# LB_BIT_i30_KEYBOARD-v03_3_4_-OHW.net
KiCad netlist of a schematic drawn in EAGLE
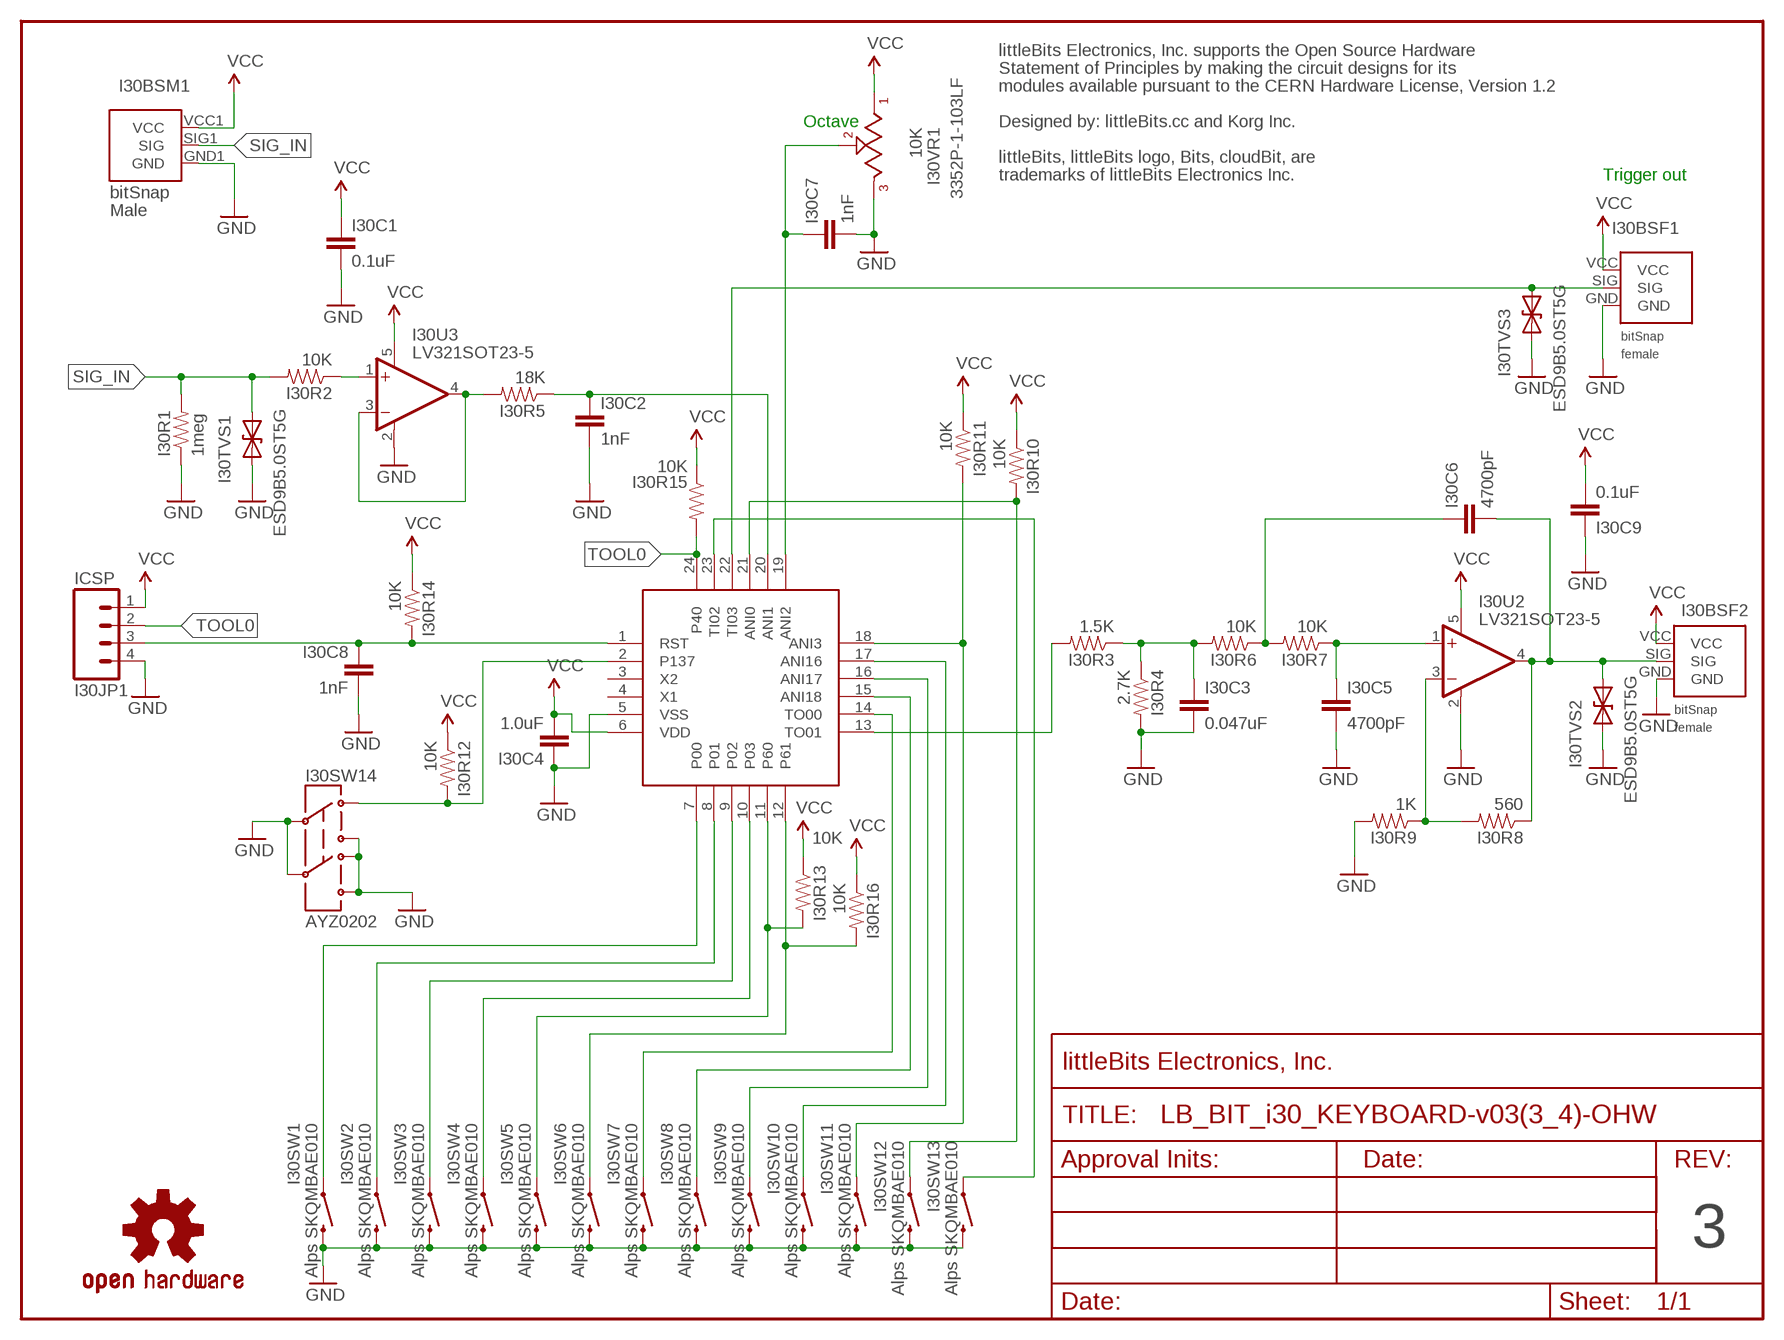
[diagram p0: schematic, sheet 1]

(export (version "E")
  (design (tool "Eeschema 10.0.6"))
  (components
    (comp (ref "FRAME1")
      (value "FRAME-LETTER-OHWOHW")
      (footprint "eagle-import:FABDWG01-OHW")
      (libsource (lib "eagle-import") (part "FRAME-LETTER-OHWOHW"))
    )
    (comp (ref "I30BSF1")
      (value "BITSNAP_V03_FEMALE")
      (footprint "eagle-import:BITSNAP_V03_FEMALE")
      (libsource (lib "eagle-import") (part "BITSNAP_V03_FEMALE"))
    )
    (comp (ref "I30BSF2")
      (value "BITSNAP_V03_FEMALE")
      (footprint "eagle-import:BITSNAP_V03_FEMALE")
      (libsource (lib "eagle-import") (part "BITSNAP_V03_FEMALE"))
    )
    (comp (ref "I30BSM1")
      (value "BITSNAP_V03_MALE")
      (footprint "eagle-import:BITSNAP_V03_MALE")
      (libsource (lib "eagle-import") (part "BITSNAP_V03_MALE"))
    )
    (comp (ref "I30C1")
      (value "0.1uF")
      (footprint "eagle-import:CAP-0603")
      (libsource (lib "eagle-import") (part "CAPCAP-0603"))
    )
    (comp (ref "I30C2")
      (value "1nF")
      (footprint "eagle-import:CAP-0603")
      (libsource (lib "eagle-import") (part "CAPCAP-0603"))
    )
    (comp (ref "I30C3")
      (value "0.047uF")
      (footprint "eagle-import:CAP-0603")
      (libsource (lib "eagle-import") (part "CAPCAP-0603"))
    )
    (comp (ref "I30C4")
      (value "1.0uF")
      (footprint "eagle-import:CAP-0603")
      (libsource (lib "eagle-import") (part "CAPCAP-0603"))
    )
    (comp (ref "I30C5")
      (value "4700pF")
      (footprint "eagle-import:CAP-0603")
      (libsource (lib "eagle-import") (part "CAPCAP-0603"))
    )
    (comp (ref "I30C6")
      (value "4700pF")
      (footprint "eagle-import:CAP-0603")
      (libsource (lib "eagle-import") (part "CAPCAP-0603"))
    )
    (comp (ref "I30C7")
      (value "1nF")
      (footprint "eagle-import:CAP-0603")
      (libsource (lib "eagle-import") (part "CAPCAP-0603"))
    )
    (comp (ref "I30C8")
      (value "1nF")
      (footprint "eagle-import:CAP-0603")
      (libsource (lib "eagle-import") (part "CAPCAP-0603"))
    )
    (comp (ref "I30C9")
      (value "0.1uF")
      (footprint "eagle-import:CAP-0603")
      (libsource (lib "eagle-import") (part "CAPCAP-0603"))
    )
    (comp (ref "I30JP1")
      (value "ICSP")
      (footprint "eagle-import:SIP4-SM-0.1IN-NOS.S.")
      (libsource (lib "eagle-import") (part "HDR-4SM_SML"))
    )
    (comp (ref "I30R1")
      (value "1meg")
      (footprint "eagle-import:RES-0603")
      (libsource (lib "eagle-import") (part "RESISTOR0603"))
    )
    (comp (ref "I30R2")
      (value "10K")
      (footprint "eagle-import:RES-0603")
      (libsource (lib "eagle-import") (part "RESISTOR0603"))
    )
    (comp (ref "I30R3")
      (value "1.5K")
      (footprint "eagle-import:RES-0603")
      (libsource (lib "eagle-import") (part "RESISTOR0603"))
    )
    (comp (ref "I30R4")
      (value "2.7K")
      (footprint "eagle-import:RES-0603")
      (libsource (lib "eagle-import") (part "RESISTOR0603"))
    )
    (comp (ref "I30R5")
      (value "18K")
      (footprint "eagle-import:RES-0603")
      (libsource (lib "eagle-import") (part "RESISTOR0603"))
    )
    (comp (ref "I30R6")
      (value "10K")
      (footprint "eagle-import:RES-0603")
      (libsource (lib "eagle-import") (part "RESISTOR0603"))
    )
    (comp (ref "I30R7")
      (value "10K")
      (footprint "eagle-import:RES-0603")
      (libsource (lib "eagle-import") (part "RESISTOR0603"))
    )
    (comp (ref "I30R8")
      (value "560")
      (footprint "eagle-import:RES-0603")
      (libsource (lib "eagle-import") (part "RESISTOR0603"))
    )
    (comp (ref "I30R9")
      (value "1K")
      (footprint "eagle-import:RES-0603")
      (libsource (lib "eagle-import") (part "RESISTOR0603"))
    )
    (comp (ref "I30R10")
      (value "10K")
      (footprint "eagle-import:RES-0603")
      (libsource (lib "eagle-import") (part "RESISTOR0603"))
    )
    (comp (ref "I30R11")
      (value "10K")
      (footprint "eagle-import:RES-0603")
      (libsource (lib "eagle-import") (part "RESISTOR0603"))
    )
    (comp (ref "I30R12")
      (value "10K")
      (footprint "eagle-import:RES-0603")
      (libsource (lib "eagle-import") (part "RESISTOR0603"))
    )
    (comp (ref "I30R13")
      (value "10K")
      (footprint "eagle-import:RES-0603")
      (libsource (lib "eagle-import") (part "RESISTOR0603"))
    )
    (comp (ref "I30R14")
      (value "10K")
      (footprint "eagle-import:RES-0603")
      (libsource (lib "eagle-import") (part "RESISTOR0603"))
    )
    (comp (ref "I30R15")
      (value "10K")
      (footprint "eagle-import:RES-0603")
      (libsource (lib "eagle-import") (part "RESISTOR0603"))
    )
    (comp (ref "I30R16")
      (value "10K")
      (footprint "eagle-import:RES-0603")
      (libsource (lib "eagle-import") (part "RESISTOR0603"))
    )
    (comp (ref "I30SW1")
      (value "Alps SKQMBAE010")
      (footprint "eagle-import:TACTILE-SWITCH-EVQ-PE104K")
      (libsource (lib "eagle-import") (part "SWITCH-MOMENTARY-2EVQ"))
    )
    (comp (ref "I30SW2")
      (value "Alps SKQMBAE010")
      (footprint "eagle-import:TACTILE-SWITCH-EVQ-PE104K")
      (libsource (lib "eagle-import") (part "SWITCH-MOMENTARY-2EVQ"))
    )
    (comp (ref "I30SW3")
      (value "Alps SKQMBAE010")
      (footprint "eagle-import:TACTILE-SWITCH-EVQ-PE104K")
      (libsource (lib "eagle-import") (part "SWITCH-MOMENTARY-2EVQ"))
    )
    (comp (ref "I30SW4")
      (value "Alps SKQMBAE010")
      (footprint "eagle-import:TACTILE-SWITCH-EVQ-PE104K")
      (libsource (lib "eagle-import") (part "SWITCH-MOMENTARY-2EVQ"))
    )
    (comp (ref "I30SW5")
      (value "Alps SKQMBAE010")
      (footprint "eagle-import:TACTILE-SWITCH-EVQ-PE104K")
      (libsource (lib "eagle-import") (part "SWITCH-MOMENTARY-2EVQ"))
    )
    (comp (ref "I30SW6")
      (value "Alps SKQMBAE010")
      (footprint "eagle-import:TACTILE-SWITCH-EVQ-PE104K")
      (libsource (lib "eagle-import") (part "SWITCH-MOMENTARY-2EVQ"))
    )
    (comp (ref "I30SW7")
      (value "Alps SKQMBAE010")
      (footprint "eagle-import:TACTILE-SWITCH-EVQ-PE104K")
      (libsource (lib "eagle-import") (part "SWITCH-MOMENTARY-2EVQ"))
    )
    (comp (ref "I30SW8")
      (value "Alps SKQMBAE010")
      (footprint "eagle-import:TACTILE-SWITCH-EVQ-PE104K")
      (libsource (lib "eagle-import") (part "SWITCH-MOMENTARY-2EVQ"))
    )
    (comp (ref "I30SW9")
      (value "Alps SKQMBAE010")
      (footprint "eagle-import:TACTILE-SWITCH-EVQ-PE104K")
      (libsource (lib "eagle-import") (part "SWITCH-MOMENTARY-2EVQ"))
    )
    (comp (ref "I30SW10")
      (value "Alps SKQMBAE010")
      (footprint "eagle-import:TACTILE-SWITCH-EVQ-PE104K")
      (libsource (lib "eagle-import") (part "SWITCH-MOMENTARY-2EVQ"))
    )
    (comp (ref "I30SW11")
      (value "Alps SKQMBAE010")
      (footprint "eagle-import:TACTILE-SWITCH-EVQ-PE104K")
      (libsource (lib "eagle-import") (part "SWITCH-MOMENTARY-2EVQ"))
    )
    (comp (ref "I30SW12")
      (value "Alps SKQMBAE010")
      (footprint "eagle-import:TACTILE-SWITCH-EVQ-PE104K")
      (libsource (lib "eagle-import") (part "SWITCH-MOMENTARY-2EVQ"))
    )
    (comp (ref "I30SW13")
      (value "Alps SKQMBAE010")
      (footprint "eagle-import:TACTILE-SWITCH-EVQ-PE104K")
      (libsource (lib "eagle-import") (part "SWITCH-MOMENTARY-2EVQ"))
    )
    (comp (ref "I30SW14")
      (value "AYZ0202")
      (footprint "eagle-import:AYZ0202")
      (libsource (lib "eagle-import") (part "AYZ0202"))
    )
    (comp (ref "I30TVS1")
      (value "ESD9B5.0ST5G")
      (footprint "eagle-import:SOD-923")
      (libsource (lib "eagle-import") (part "DIODE-TVSSOD-923"))
    )
    (comp (ref "I30TVS2")
      (value "ESD9B5.0ST5G")
      (footprint "eagle-import:SOD-923")
      (libsource (lib "eagle-import") (part "DIODE-TVSSOD-923"))
    )
    (comp (ref "I30TVS3")
      (value "ESD9B5.0ST5G")
      (footprint "eagle-import:SOD-923")
      (libsource (lib "eagle-import") (part "DIODE-TVSSOD-923"))
    )
    (comp (ref "I30U1")
      (value "R5F10278QFN-24")
      (footprint "eagle-import:QFN-24(4MM)")
      (libsource (lib "eagle-import") (part "R5F10278QFN-24"))
    )
    (comp (ref "I30U2")
      (value "LV321SOT23-5")
      (footprint "eagle-import:SOT23-5")
      (libsource (lib "eagle-import") (part "LV321SOT23-5"))
    )
    (comp (ref "I30U3")
      (value "LV321SOT23-5")
      (footprint "eagle-import:SOT23-5")
      (libsource (lib "eagle-import") (part "LV321SOT23-5"))
    )
    (comp (ref "I30VR1")
      (value "10K")
      (footprint "eagle-import:THUMBPOT-BOURNS_3352")
      (libsource (lib "eagle-import") (part "THUMBPOT-BOURNS_3352P"))
    )
    (comp (ref "U$1")
      (value "OSHW-LOGOL")
      (footprint "eagle-import:OSHW-LOGO-L")
      (libsource (lib "eagle-import") (part "OSHW-LOGOL"))
    )
    (comp (ref "U$2")
      (value "OSHWCREDIT-KORG")
      (footprint "eagle-import:OSHWCREDIT-KORG")
      (libsource (lib "eagle-import") (part "OSHWCREDIT-KORG"))
    )
  )
  (nets
    (net (code "1") (name "GND") (class "Default")
      (node (ref "I30BSF1") (pin "GND") (pinfunction "GND_GND") (pintype "bidirectional"))
      (node (ref "I30BSF2") (pin "GND") (pinfunction "GND_GND") (pintype "bidirectional"))
      (node (ref "I30BSM1") (pin "GND1") (pinfunction "GND_GND1") (pintype "bidirectional"))
      (node (ref "I30C1") (pin "2") (pinfunction "2_2") (pintype "passive"))
      (node (ref "I30C2") (pin "2") (pinfunction "2_2") (pintype "passive"))
      (node (ref "I30C3") (pin "2") (pinfunction "2_2") (pintype "passive"))
      (node (ref "I30C4") (pin "1") (pinfunction "1_1") (pintype "passive"))
      (node (ref "I30C5") (pin "2") (pinfunction "2_2") (pintype "passive"))
      (node (ref "I30C7") (pin "2") (pinfunction "2_2") (pintype "passive"))
      (node (ref "I30C8") (pin "2") (pinfunction "2_2") (pintype "passive"))
      (node (ref "I30C9") (pin "1") (pinfunction "1_1") (pintype "passive"))
      (node (ref "I30JP1") (pin "4") (pinfunction "4_4") (pintype "passive"))
      (node (ref "I30R1") (pin "1") (pinfunction "1_1") (pintype "passive"))
      (node (ref "I30R4") (pin "2") (pinfunction "2_2") (pintype "passive"))
      (node (ref "I30R9") (pin "2") (pinfunction "2_2") (pintype "passive"))
      (node (ref "I30SW1") (pin "P$2") (pinfunction "2_P$2") (pintype "passive"))
      (node (ref "I30SW10") (pin "P$2") (pinfunction "2_P$2") (pintype "passive"))
      (node (ref "I30SW11") (pin "P$2") (pinfunction "2_P$2") (pintype "passive"))
      (node (ref "I30SW12") (pin "P$2") (pinfunction "2_P$2") (pintype "passive"))
      (node (ref "I30SW13") (pin "P$2") (pinfunction "2_P$2") (pintype "passive"))
      (node (ref "I30SW14") (pin "2") (pinfunction "2_2") (pintype "bidirectional"))
      (node (ref "I30SW14") (pin "3") (pinfunction "3_3") (pintype "bidirectional"))
      (node (ref "I30SW14") (pin "4") (pinfunction "4_4") (pintype "bidirectional"))
      (node (ref "I30SW14") (pin "5") (pinfunction "5_5") (pintype "bidirectional"))
      (node (ref "I30SW14") (pin "6") (pinfunction "6_6") (pintype "bidirectional"))
      (node (ref "I30SW2") (pin "P$2") (pinfunction "2_P$2") (pintype "passive"))
      (node (ref "I30SW3") (pin "P$2") (pinfunction "2_P$2") (pintype "passive"))
      (node (ref "I30SW4") (pin "P$2") (pinfunction "2_P$2") (pintype "passive"))
      (node (ref "I30SW5") (pin "P$2") (pinfunction "2_P$2") (pintype "passive"))
      (node (ref "I30SW6") (pin "P$2") (pinfunction "2_P$2") (pintype "passive"))
      (node (ref "I30SW7") (pin "P$2") (pinfunction "2_P$2") (pintype "passive"))
      (node (ref "I30SW8") (pin "P$2") (pinfunction "2_P$2") (pintype "passive"))
      (node (ref "I30SW9") (pin "P$2") (pinfunction "2_P$2") (pintype "passive"))
      (node (ref "I30TVS1") (pin "1") (pinfunction "A_1") (pintype "passive"))
      (node (ref "I30TVS2") (pin "1") (pinfunction "A_1") (pintype "passive"))
      (node (ref "I30TVS3") (pin "1") (pinfunction "A_1") (pintype "passive"))
      (node (ref "I30U1") (pin "5") (pinfunction "VSS_5") (pintype "bidirectional"))
      (node (ref "I30U2") (pin "2") (pinfunction "V-_2") (pintype "power_in"))
      (node (ref "I30U3") (pin "2") (pinfunction "V-_2") (pintype "power_in"))
      (node (ref "I30VR1") (pin "1") (pinfunction "3_1") (pintype "passive"))
    )
    (net (code "2") (name "Net-(I30C3-Pad1)") (class "Default")
      (node (ref "I30C3") (pin "1") (pinfunction "1_1") (pintype "passive"))
      (node (ref "I30R3") (pin "1") (pinfunction "1_1") (pintype "passive"))
      (node (ref "I30R4") (pin "1") (pinfunction "1_1") (pintype "passive"))
      (node (ref "I30R6") (pin "2") (pinfunction "2_2") (pintype "passive"))
    )
    (net (code "3") (name "Net-(I30C6-Pad1)") (class "Default")
      (node (ref "I30C6") (pin "1") (pinfunction "1_1") (pintype "passive"))
      (node (ref "I30R6") (pin "1") (pinfunction "1_1") (pintype "passive"))
      (node (ref "I30R7") (pin "2") (pinfunction "2_2") (pintype "passive"))
    )
    (net (code "4") (name "Net-(I30SW1-1)") (class "Default")
      (node (ref "I30SW1") (pin "P$1") (pinfunction "1_P$1") (pintype "passive"))
      (node (ref "I30U1") (pin "7") (pinfunction "P00_7") (pintype "bidirectional"))
    )
    (net (code "5") (name "Net-(I30SW2-1)") (class "Default")
      (node (ref "I30SW2") (pin "P$1") (pinfunction "1_P$1") (pintype "passive"))
      (node (ref "I30U1") (pin "8") (pinfunction "P01_8") (pintype "bidirectional"))
    )
    (net (code "6") (name "Net-(I30SW3-1)") (class "Default")
      (node (ref "I30SW3") (pin "P$1") (pinfunction "1_P$1") (pintype "passive"))
      (node (ref "I30U1") (pin "9") (pinfunction "P02_9") (pintype "bidirectional"))
    )
    (net (code "7") (name "Net-(I30SW4-1)") (class "Default")
      (node (ref "I30SW4") (pin "P$1") (pinfunction "1_P$1") (pintype "passive"))
      (node (ref "I30U1") (pin "10") (pinfunction "P03_10") (pintype "bidirectional"))
    )
    (net (code "8") (name "Net-(I30SW5-1)") (class "Default")
      (node (ref "I30R13") (pin "2") (pinfunction "2_2") (pintype "passive"))
      (node (ref "I30SW5") (pin "P$1") (pinfunction "1_P$1") (pintype "passive"))
      (node (ref "I30U1") (pin "11") (pinfunction "P60_11") (pintype "bidirectional"))
    )
    (net (code "9") (name "Net-(I30SW6-1)") (class "Default")
      (node (ref "I30R16") (pin "2") (pinfunction "2_2") (pintype "passive"))
      (node (ref "I30SW6") (pin "P$1") (pinfunction "1_P$1") (pintype "passive"))
      (node (ref "I30U1") (pin "12") (pinfunction "P61_12") (pintype "bidirectional"))
    )
    (net (code "10") (name "Net-(I30SW7-1)") (class "Default")
      (node (ref "I30SW7") (pin "P$1") (pinfunction "1_P$1") (pintype "passive"))
      (node (ref "I30U1") (pin "14") (pinfunction "TO00_14") (pintype "bidirectional"))
    )
    (net (code "11") (name "Net-(I30SW8-1)") (class "Default")
      (node (ref "I30SW8") (pin "P$1") (pinfunction "1_P$1") (pintype "passive"))
      (node (ref "I30U1") (pin "15") (pinfunction "ANI18_15") (pintype "bidirectional"))
    )
    (net (code "12") (name "Net-(I30SW9-1)") (class "Default")
      (node (ref "I30SW9") (pin "P$1") (pinfunction "1_P$1") (pintype "passive"))
      (node (ref "I30U1") (pin "16") (pinfunction "ANI17_16") (pintype "bidirectional"))
    )
    (net (code "13") (name "Net-(I30SW10-1)") (class "Default")
      (node (ref "I30SW10") (pin "P$1") (pinfunction "1_P$1") (pintype "passive"))
      (node (ref "I30U1") (pin "17") (pinfunction "ANI16_17") (pintype "bidirectional"))
    )
    (net (code "14") (name "Net-(I30SW11-1)") (class "Default")
      (node (ref "I30R11") (pin "2") (pinfunction "2_2") (pintype "passive"))
      (node (ref "I30SW11") (pin "P$1") (pinfunction "1_P$1") (pintype "passive"))
      (node (ref "I30U1") (pin "18") (pinfunction "ANI3_18") (pintype "bidirectional"))
    )
    (net (code "15") (name "Net-(I30SW12-1)") (class "Default")
      (node (ref "I30R10") (pin "2") (pinfunction "2_2") (pintype "passive"))
      (node (ref "I30SW12") (pin "P$1") (pinfunction "1_P$1") (pintype "passive"))
      (node (ref "I30U1") (pin "21") (pinfunction "ANI0_21") (pintype "bidirectional"))
    )
    (net (code "16") (name "Net-(I30SW13-1)") (class "Default")
      (node (ref "I30SW13") (pin "P$1") (pinfunction "1_P$1") (pintype "passive"))
      (node (ref "I30U1") (pin "23") (pinfunction "TI02_23") (pintype "bidirectional"))
    )
    (net (code "17") (name "Net-(I30TVS2-C)") (class "Default")
      (node (ref "I30BSF2") (pin "SIG") (pinfunction "SIG_SIG") (pintype "bidirectional"))
      (node (ref "I30C6") (pin "2") (pinfunction "2_2") (pintype "passive"))
      (node (ref "I30R8") (pin "1") (pinfunction "1_1") (pintype "passive"))
      (node (ref "I30TVS2") (pin "2") (pinfunction "C_2") (pintype "passive"))
      (node (ref "I30U2") (pin "4") (pinfunction "OUT_4") (pintype "output"))
    )
    (net (code "18") (name "Net-(I30TVS3-C)") (class "Default")
      (node (ref "I30BSF1") (pin "SIG") (pinfunction "SIG_SIG") (pintype "bidirectional"))
      (node (ref "I30TVS3") (pin "2") (pinfunction "C_2") (pintype "passive"))
      (node (ref "I30U1") (pin "22") (pinfunction "TI03_22") (pintype "bidirectional"))
    )
    (net (code "19") (name "Net-(I30U1-ANI1)") (class "Default")
      (node (ref "I30C2") (pin "1") (pinfunction "1_1") (pintype "passive"))
      (node (ref "I30R5") (pin "1") (pinfunction "1_1") (pintype "passive"))
      (node (ref "I30U1") (pin "20") (pinfunction "ANI1_20") (pintype "bidirectional"))
    )
    (net (code "20") (name "Net-(I30U1-ANI2)") (class "Default")
      (node (ref "I30C7") (pin "1") (pinfunction "1_1") (pintype "passive"))
      (node (ref "I30U1") (pin "19") (pinfunction "ANI2_19") (pintype "bidirectional"))
      (node (ref "I30VR1") (pin "2") (pinfunction "2_2") (pintype "passive"))
    )
    (net (code "21") (name "Net-(I30U1-P137)") (class "Default")
      (node (ref "I30R12") (pin "2") (pinfunction "2_2") (pintype "passive"))
      (node (ref "I30SW14") (pin "1") (pinfunction "1_1") (pintype "bidirectional"))
      (node (ref "I30U1") (pin "2") (pinfunction "P137_2") (pintype "bidirectional"))
    )
    (net (code "22") (name "Net-(I30U1-RST)") (class "Default")
      (node (ref "I30C8") (pin "1") (pinfunction "1_1") (pintype "passive"))
      (node (ref "I30JP1") (pin "3") (pinfunction "3_3") (pintype "passive"))
      (node (ref "I30R14") (pin "2") (pinfunction "2_2") (pintype "passive"))
      (node (ref "I30U1") (pin "1") (pinfunction "RST_1") (pintype "bidirectional"))
    )
    (net (code "23") (name "Net-(I30U1-TO01)") (class "Default")
      (node (ref "I30R3") (pin "2") (pinfunction "2_2") (pintype "passive"))
      (node (ref "I30U1") (pin "13") (pinfunction "TO01_13") (pintype "bidirectional"))
    )
    (net (code "24") (name "Net-(I30U2-+IN)") (class "Default")
      (node (ref "I30C5") (pin "1") (pinfunction "1_1") (pintype "passive"))
      (node (ref "I30R7") (pin "1") (pinfunction "1_1") (pintype "passive"))
      (node (ref "I30U2") (pin "1") (pinfunction "+IN_1") (pintype "input"))
    )
    (net (code "25") (name "Net-(I30U2--IN)") (class "Default")
      (node (ref "I30R8") (pin "2") (pinfunction "2_2") (pintype "passive"))
      (node (ref "I30R9") (pin "1") (pinfunction "1_1") (pintype "passive"))
      (node (ref "I30U2") (pin "3") (pinfunction "-IN_3") (pintype "input"))
    )
    (net (code "26") (name "Net-(I30U3-+IN)") (class "Default")
      (node (ref "I30R2") (pin "1") (pinfunction "1_1") (pintype "passive"))
      (node (ref "I30U3") (pin "1") (pinfunction "+IN_1") (pintype "input"))
    )
    (net (code "27") (name "Net-(I30U3--IN)") (class "Default")
      (node (ref "I30R5") (pin "2") (pinfunction "2_2") (pintype "passive"))
      (node (ref "I30U3") (pin "3") (pinfunction "-IN_3") (pintype "input"))
      (node (ref "I30U3") (pin "4") (pinfunction "OUT_4") (pintype "output"))
    )
    (net (code "28") (name "SIG_IN") (class "Default")
      (node (ref "I30BSM1") (pin "SIG1") (pinfunction "SIG_SIG1") (pintype "bidirectional"))
      (node (ref "I30R1") (pin "2") (pinfunction "2_2") (pintype "passive"))
      (node (ref "I30R2") (pin "2") (pinfunction "2_2") (pintype "passive"))
      (node (ref "I30TVS1") (pin "2") (pinfunction "C_2") (pintype "passive"))
    )
    (net (code "29") (name "TOOL0") (class "Default")
      (node (ref "I30JP1") (pin "2") (pinfunction "2_2") (pintype "passive"))
      (node (ref "I30R15") (pin "2") (pinfunction "2_2") (pintype "passive"))
      (node (ref "I30U1") (pin "24") (pinfunction "P40_24") (pintype "bidirectional"))
    )
    (net (code "30") (name "VCC") (class "Default")
      (node (ref "I30BSF1") (pin "VCC") (pinfunction "VCC_VCC") (pintype "bidirectional"))
      (node (ref "I30BSF2") (pin "VCC") (pinfunction "VCC_VCC") (pintype "bidirectional"))
      (node (ref "I30BSM1") (pin "VCC1") (pinfunction "VCC_VCC1") (pintype "bidirectional"))
      (node (ref "I30C1") (pin "1") (pinfunction "1_1") (pintype "passive"))
      (node (ref "I30C4") (pin "2") (pinfunction "2_2") (pintype "passive"))
      (node (ref "I30C9") (pin "2") (pinfunction "2_2") (pintype "passive"))
      (node (ref "I30JP1") (pin "1") (pinfunction "1_1") (pintype "passive"))
      (node (ref "I30R10") (pin "1") (pinfunction "1_1") (pintype "passive"))
      (node (ref "I30R11") (pin "1") (pinfunction "1_1") (pintype "passive"))
      (node (ref "I30R12") (pin "1") (pinfunction "1_1") (pintype "passive"))
      (node (ref "I30R13") (pin "1") (pinfunction "1_1") (pintype "passive"))
      (node (ref "I30R14") (pin "1") (pinfunction "1_1") (pintype "passive"))
      (node (ref "I30R15") (pin "1") (pinfunction "1_1") (pintype "passive"))
      (node (ref "I30R16") (pin "1") (pinfunction "1_1") (pintype "passive"))
      (node (ref "I30U1") (pin "6") (pinfunction "VDD_6") (pintype "bidirectional"))
      (node (ref "I30U2") (pin "5") (pinfunction "V+_5") (pintype "power_in"))
      (node (ref "I30U3") (pin "5") (pinfunction "V+_5") (pintype "power_in"))
      (node (ref "I30VR1") (pin "3") (pinfunction "1_3") (pintype "passive"))
    )
    (net (code "31") (name "unconnected-(I30U1-X1-Pad4)") (class "Default")
      (node (ref "I30U1") (pin "4") (pinfunction "X1_4") (pintype "bidirectional"))
    )
    (net (code "32") (name "unconnected-(I30U1-X2-Pad3)") (class "Default")
      (node (ref "I30U1") (pin "3") (pinfunction "X2_3") (pintype "bidirectional"))
    )
  )
)
